# ChargerModule.net
KiCad netlist of a schematic drawn in EAGLE
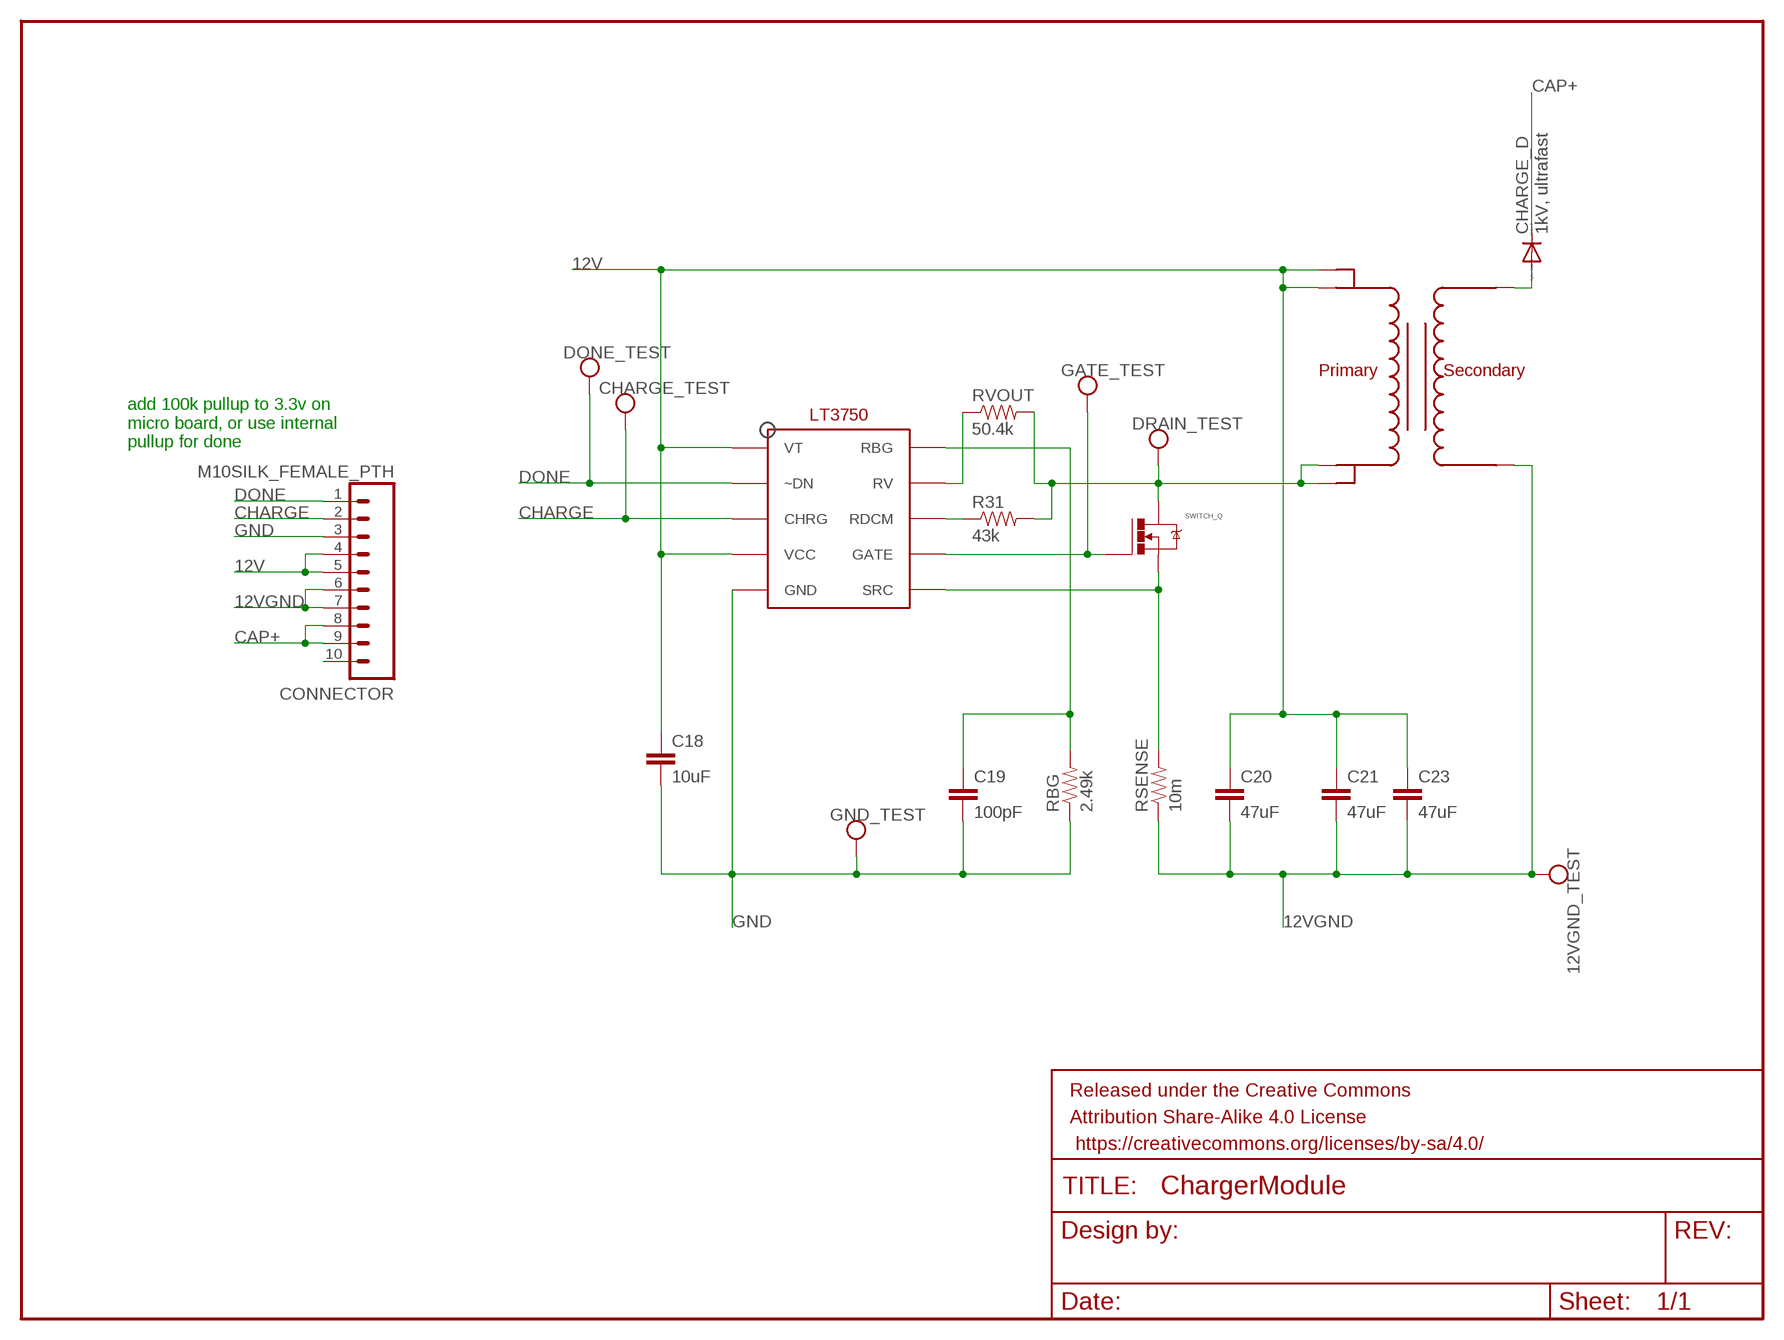
[diagram p0: schematic, sheet 1]

(export (version "E")
  (design (tool "Eeschema 10.0.6"))
  (components
    (comp (ref "12VGND_TEST")
      (value "TEST_PT")
      (footprint "eagle-import:TESTING_PT")
      (libsource (lib "eagle-import") (part "TEST_PT"))
    )
    (comp (ref "C18")
      (value "10uF")
      (footprint "eagle-import:0805")
      (libsource (lib "eagle-import") (part "CAP0805"))
    )
    (comp (ref "C19")
      (value "100pF")
      (footprint "eagle-import:0805")
      (libsource (lib "eagle-import") (part "CAP0805"))
    )
    (comp (ref "C20")
      (value "47uF")
      (footprint "eagle-import:1206")
      (libsource (lib "eagle-import") (part "CAP1206"))
    )
    (comp (ref "C21")
      (value "47uF")
      (footprint "eagle-import:1206")
      (libsource (lib "eagle-import") (part "CAP1206"))
    )
    (comp (ref "C23")
      (value "47uF")
      (footprint "eagle-import:1206")
      (libsource (lib "eagle-import") (part "CAP1206"))
    )
    (comp (ref "CHARGE_D")
      (value "1kV, ultrafast")
      (footprint "eagle-import:DO214AC")
      (libsource (lib "eagle-import") (part "DIODE-DO214AC"))
    )
    (comp (ref "CHARGE_TEST")
      (value "TEST_PT")
      (footprint "eagle-import:TESTING_PT")
      (libsource (lib "eagle-import") (part "TEST_PT"))
    )
    (comp (ref "CHARGE_U")
      (value "LT3750")
      (footprint "eagle-import:10-MSOP")
      (libsource (lib "eagle-import") (part "LT3750"))
    )
    (comp (ref "CONNECTOR")
      (value "M10SILK_FEMALE_PTH")
      (footprint "eagle-import:1X10")
      (libsource (lib "eagle-import") (part "M10SILK_FEMALE_PTH"))
    )
    (comp (ref "DONE_TEST")
      (value "TEST_PT")
      (footprint "eagle-import:TESTING_PT")
      (libsource (lib "eagle-import") (part "TEST_PT"))
    )
    (comp (ref "DRAIN_TEST")
      (value "TEST_PT")
      (footprint "eagle-import:TESTING_PT")
      (libsource (lib "eagle-import") (part "TEST_PT"))
    )
    (comp (ref "FRAME3")
      (value "FRAME-LETTER")
      (footprint "eagle-import:CREATIVE_COMMONS")
      (libsource (lib "eagle-import") (part "FRAME-LETTER"))
    )
    (comp (ref "GATE_TEST")
      (value "TEST_PT")
      (footprint "eagle-import:TESTING_PT")
      (libsource (lib "eagle-import") (part "TEST_PT"))
    )
    (comp (ref "GND_TEST")
      (value "TEST_PT")
      (footprint "eagle-import:TESTING_PT")
      (libsource (lib "eagle-import") (part "TEST_PT"))
    )
    (comp (ref "R31")
      (value "43k")
      (footprint "eagle-import:0805")
      (libsource (lib "eagle-import") (part "RESISTOR0805-RES"))
    )
    (comp (ref "RBG")
      (value "2.49k")
      (footprint "eagle-import:0805")
      (libsource (lib "eagle-import") (part "RESISTOR0805-RES"))
    )
    (comp (ref "RSENSE")
      (value "10m")
      (footprint "eagle-import:R2512")
      (libsource (lib "eagle-import") (part "RESISTOR2512"))
    )
    (comp (ref "RVOUT")
      (value "50.4k")
      (footprint "eagle-import:0805")
      (libsource (lib "eagle-import") (part "RESISTOR0805-RES"))
    )
    (comp (ref "SWITCH_Q")
      (value "N-MOSFETDPAK")
      (footprint "eagle-import:DPAK")
      (libsource (lib "eagle-import") (part "N-MOSFETDPAK"))
    )
    (comp (ref "U$1")
      (value "32052-TRANSFORMER")
      (footprint "eagle-import:10-TRANSFORMER")
      (libsource (lib "eagle-import") (part "32052-TRANSFORMER"))
    )
  )
  (nets
    (net (code "1") (name "/12V") (class "Default")
      (node (ref "C18") (pin "1") (pinfunction "1_1") (pintype "passive"))
      (node (ref "C20") (pin "1") (pinfunction "1_1") (pintype "passive"))
      (node (ref "C21") (pin "1") (pinfunction "1_1") (pintype "passive"))
      (node (ref "C23") (pin "1") (pinfunction "1_1") (pintype "passive"))
      (node (ref "CHARGE_U") (pin "P$1") (pinfunction "VT_P$1") (pintype "bidirectional"))
      (node (ref "CHARGE_U") (pin "P$4") (pinfunction "VCC_P$4") (pintype "bidirectional"))
      (node (ref "CONNECTOR") (pin "4") (pinfunction "4_4") (pintype "passive"))
      (node (ref "CONNECTOR") (pin "5") (pinfunction "5_5") (pintype "passive"))
      (node (ref "U$1") (pin "P$4") (pinfunction "P$4_P$4") (pintype "bidirectional"))
      (node (ref "U$1") (pin "P$5") (pinfunction "P$5_P$5") (pintype "bidirectional"))
    )
    (net (code "2") (name "/12VGND") (class "Default")
      (node (ref "12VGND_TEST") (pin "P$1") (pinfunction "P$1_P$1") (pintype "bidirectional"))
      (node (ref "C20") (pin "2") (pinfunction "2_2") (pintype "passive"))
      (node (ref "C21") (pin "2") (pinfunction "2_2") (pintype "passive"))
      (node (ref "C23") (pin "2") (pinfunction "2_2") (pintype "passive"))
      (node (ref "CONNECTOR") (pin "6") (pinfunction "6_6") (pintype "passive"))
      (node (ref "CONNECTOR") (pin "7") (pinfunction "7_7") (pintype "passive"))
      (node (ref "RSENSE") (pin "1") (pinfunction "1_1") (pintype "passive"))
      (node (ref "U$1") (pin "P$10") (pinfunction "P$10_P$10") (pintype "bidirectional"))
    )
    (net (code "3") (name "/CAP+") (class "Default")
      (node (ref "CHARGE_D") (pin "C") (pinfunction "C_C") (pintype "passive"))
      (node (ref "CONNECTOR") (pin "8") (pinfunction "8_8") (pintype "passive"))
      (node (ref "CONNECTOR") (pin "9") (pinfunction "9_9") (pintype "passive"))
    )
    (net (code "4") (name "/CHARGE") (class "Default")
      (node (ref "CHARGE_TEST") (pin "P$1") (pinfunction "P$1_P$1") (pintype "bidirectional"))
      (node (ref "CHARGE_U") (pin "P$3") (pinfunction "CHRG_P$3") (pintype "bidirectional"))
      (node (ref "CONNECTOR") (pin "2") (pinfunction "2_2") (pintype "passive"))
    )
    (net (code "5") (name "/DONE") (class "Default")
      (node (ref "CHARGE_U") (pin "P$2") (pinfunction "~{DN}_P$2") (pintype "bidirectional"))
      (node (ref "CONNECTOR") (pin "1") (pinfunction "1_1") (pintype "passive"))
      (node (ref "DONE_TEST") (pin "P$1") (pinfunction "P$1_P$1") (pintype "bidirectional"))
    )
    (net (code "6") (name "/GND") (class "Default")
      (node (ref "C18") (pin "2") (pinfunction "2_2") (pintype "passive"))
      (node (ref "C19") (pin "2") (pinfunction "2_2") (pintype "passive"))
      (node (ref "CHARGE_U") (pin "P$5") (pinfunction "GND_P$5") (pintype "bidirectional"))
      (node (ref "CONNECTOR") (pin "3") (pinfunction "3_3") (pintype "passive"))
      (node (ref "GND_TEST") (pin "P$1") (pinfunction "P$1_P$1") (pintype "bidirectional"))
      (node (ref "RBG") (pin "1") (pinfunction "1_1") (pintype "passive"))
    )
    (net (code "7") (name "Net-(CHARGE_D-PadA)") (class "Default")
      (node (ref "CHARGE_D") (pin "A") (pinfunction "A_A") (pintype "passive"))
      (node (ref "U$1") (pin "P$1") (pinfunction "P$1_P$1") (pintype "bidirectional"))
    )
    (net (code "8") (name "Net-(CHARGE_U-GATE)") (class "Default")
      (node (ref "CHARGE_U") (pin "P$7") (pinfunction "GATE_P$7") (pintype "bidirectional"))
      (node (ref "GATE_TEST") (pin "P$1") (pinfunction "P$1_P$1") (pintype "bidirectional"))
      (node (ref "SWITCH_Q") (pin "GATE") (pinfunction "G_GATE") (pintype "bidirectional"))
    )
    (net (code "9") (name "Net-(CHARGE_U-RBG)") (class "Default")
      (node (ref "C19") (pin "1") (pinfunction "1_1") (pintype "passive"))
      (node (ref "CHARGE_U") (pin "P$10") (pinfunction "RBG_P$10") (pintype "bidirectional"))
      (node (ref "RBG") (pin "2") (pinfunction "2_2") (pintype "passive"))
    )
    (net (code "10") (name "Net-(CHARGE_U-RDCM)") (class "Default")
      (node (ref "CHARGE_U") (pin "P$8") (pinfunction "RDCM_P$8") (pintype "bidirectional"))
      (node (ref "R31") (pin "1") (pinfunction "1_1") (pintype "passive"))
    )
    (net (code "11") (name "Net-(CHARGE_U-RV)") (class "Default")
      (node (ref "CHARGE_U") (pin "P$9") (pinfunction "RV_P$9") (pintype "bidirectional"))
      (node (ref "RVOUT") (pin "1") (pinfunction "1_1") (pintype "passive"))
    )
    (net (code "12") (name "Net-(CHARGE_U-SRC)") (class "Default")
      (node (ref "CHARGE_U") (pin "P$6") (pinfunction "SRC_P$6") (pintype "bidirectional"))
      (node (ref "RSENSE") (pin "2") (pinfunction "2_2") (pintype "passive"))
      (node (ref "SWITCH_Q") (pin "SOURCE") (pinfunction "S_SOURCE") (pintype "bidirectional"))
    )
    (net (code "13") (name "Net-(SWITCH_Q-D)") (class "Default")
      (node (ref "DRAIN_TEST") (pin "P$1") (pinfunction "P$1_P$1") (pintype "bidirectional"))
      (node (ref "R31") (pin "2") (pinfunction "2_2") (pintype "passive"))
      (node (ref "RVOUT") (pin "2") (pinfunction "2_2") (pintype "passive"))
      (node (ref "SWITCH_Q") (pin "DRAIN") (pinfunction "D_DRAIN") (pintype "bidirectional"))
      (node (ref "U$1") (pin "P$6") (pinfunction "P$6_P$6") (pintype "bidirectional"))
      (node (ref "U$1") (pin "P$7") (pinfunction "P$7_P$7") (pintype "bidirectional"))
    )
    (net (code "14") (name "unconnected-(CONNECTOR-Pad10)") (class "Default")
      (node (ref "CONNECTOR") (pin "10") (pinfunction "10_10") (pintype "passive"))
    )
  )
)
